# delay_v03.net
KiCad netlist of a schematic drawn in EAGLE
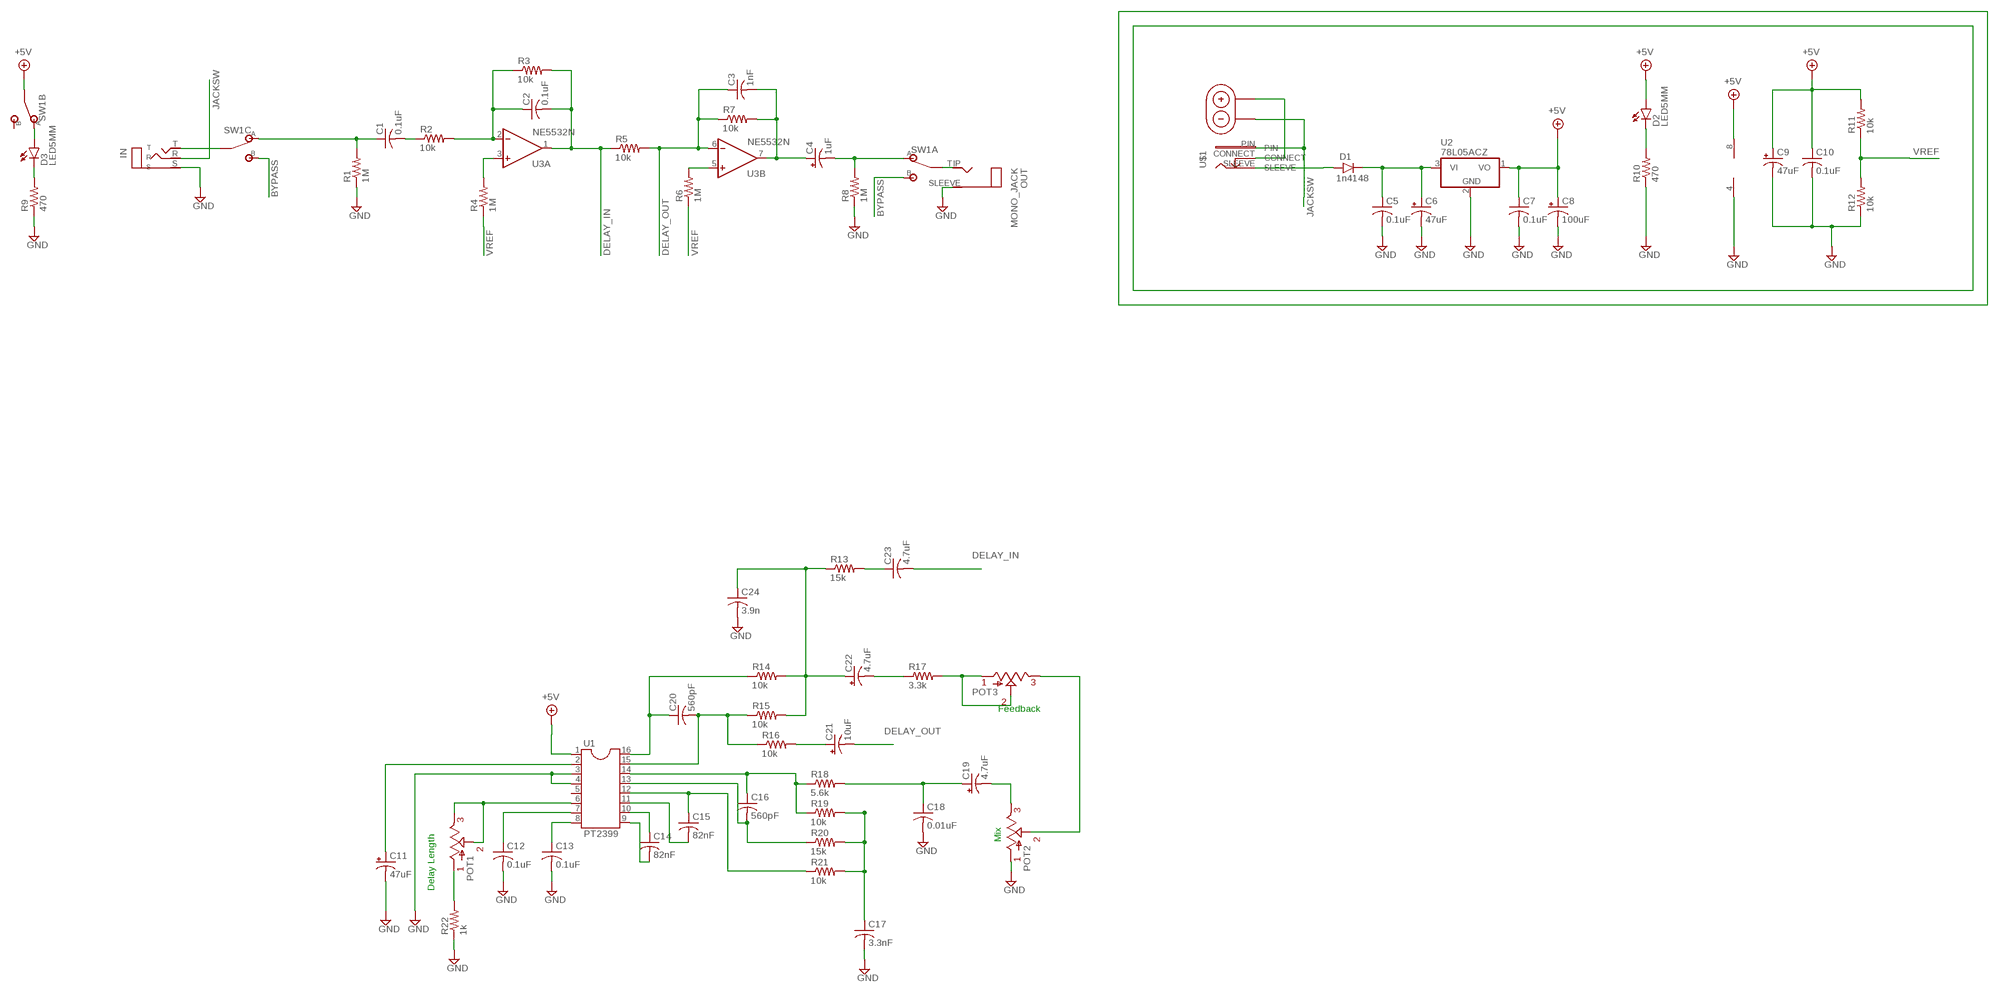
[diagram p0: schematic, sheet 1]

(export (version "E")
  (design (tool "Eeschema 10.0.6"))
  (components
    (comp (ref "C1")
      (value "0.1uF")
      (footprint "eagle-import:C050-035X075")
      (libsource (lib "eagle-import") (part "C-US050-035X075"))
    )
    (comp (ref "C2")
      (value "0.1uF")
      (footprint "eagle-import:C050-035X075")
      (libsource (lib "eagle-import") (part "C-US050-035X075"))
    )
    (comp (ref "C3")
      (value "1nF")
      (footprint "eagle-import:C050-035X075")
      (libsource (lib "eagle-import") (part "C-US050-035X075"))
    )
    (comp (ref "C4")
      (value "1uF")
      (footprint "eagle-import:063_025")
      (libsource (lib "eagle-import") (part "0631"))
    )
    (comp (ref "C5")
      (value "0.1uF")
      (footprint "eagle-import:C050-035X075")
      (libsource (lib "eagle-import") (part "C-US050-035X075"))
    )
    (comp (ref "C6")
      (value "47uF")
      (footprint "eagle-import:063_025")
      (libsource (lib "eagle-import") (part "0631"))
    )
    (comp (ref "C7")
      (value "0.1uF")
      (footprint "eagle-import:C050-035X075")
      (libsource (lib "eagle-import") (part "C-US050-035X075"))
    )
    (comp (ref "C8")
      (value "100uF")
      (footprint "eagle-import:063_025")
      (libsource (lib "eagle-import") (part "0631"))
    )
    (comp (ref "C9")
      (value "47uF")
      (footprint "eagle-import:063_025")
      (libsource (lib "eagle-import") (part "0631"))
    )
    (comp (ref "C10")
      (value "0.1uF")
      (footprint "eagle-import:C050-035X075")
      (libsource (lib "eagle-import") (part "C-US050-035X075"))
    )
    (comp (ref "C11")
      (value "47uF")
      (footprint "eagle-import:063_025")
      (libsource (lib "eagle-import") (part "0631"))
    )
    (comp (ref "C12")
      (value "0.1uF")
      (footprint "eagle-import:C050-035X075")
      (libsource (lib "eagle-import") (part "C-US050-035X075"))
    )
    (comp (ref "C13")
      (value "0.1uF")
      (footprint "eagle-import:C050-035X075")
      (libsource (lib "eagle-import") (part "C-US050-035X075"))
    )
    (comp (ref "C14")
      (value "82nF")
      (footprint "eagle-import:C050-035X075")
      (libsource (lib "eagle-import") (part "C-US050-035X075"))
    )
    (comp (ref "C15")
      (value "82nF")
      (footprint "eagle-import:C050-035X075")
      (libsource (lib "eagle-import") (part "C-US050-035X075"))
    )
    (comp (ref "C16")
      (value "560pF")
      (footprint "eagle-import:C050-035X075")
      (libsource (lib "eagle-import") (part "C-US050-035X075"))
    )
    (comp (ref "C17")
      (value "3.3nF")
      (footprint "eagle-import:C050-035X075")
      (libsource (lib "eagle-import") (part "C-US050-035X075"))
    )
    (comp (ref "C18")
      (value "0.01uF")
      (footprint "eagle-import:C050-035X075")
      (libsource (lib "eagle-import") (part "C-US050-035X075"))
    )
    (comp (ref "C19")
      (value "4.7uF")
      (footprint "eagle-import:063_025")
      (libsource (lib "eagle-import") (part "0631"))
    )
    (comp (ref "C20")
      (value "560pF")
      (footprint "eagle-import:C050-035X075")
      (libsource (lib "eagle-import") (part "C-US050-035X075"))
    )
    (comp (ref "C21")
      (value "10uF")
      (footprint "eagle-import:063_025")
      (libsource (lib "eagle-import") (part "0631"))
    )
    (comp (ref "C22")
      (value "4.7uF")
      (footprint "eagle-import:063_025")
      (libsource (lib "eagle-import") (part "0631"))
    )
    (comp (ref "C23")
      (value "4.7uF")
      (footprint "eagle-import:C050-035X075")
      (libsource (lib "eagle-import") (part "C-US050-035X075"))
    )
    (comp (ref "C24")
      (value "3.9n")
      (footprint "eagle-import:C050-035X075")
      (libsource (lib "eagle-import") (part "C-US050-035X075"))
    )
    (comp (ref "D1")
      (value "1n4148")
      (footprint "eagle-import:DO41-3")
      (libsource (lib "eagle-import") (part "1N400X.3"))
    )
    (comp (ref "D2")
      (value "LED5MM")
      (footprint "eagle-import:LED5MM")
      (libsource (lib "eagle-import") (part "LED5MM"))
    )
    (comp (ref "D3")
      (value "LED5MM")
      (footprint "eagle-import:LED5MM")
      (libsource (lib "eagle-import") (part "LED5MM"))
    )
    (comp (ref "IN")
      (value "STEREO_JACK")
      (footprint "eagle-import:STEREO_JACK")
      (libsource (lib "eagle-import") (part "STEREO_JACK"))
    )
    (comp (ref "OUT")
      (value "MONO_JACK")
      (footprint "eagle-import:MONO_JACK")
      (libsource (lib "eagle-import") (part "MONO_JACK"))
    )
    (comp (ref "POT1")
      (value "POT")
      (footprint "eagle-import:POT")
      (libsource (lib "eagle-import") (part "POT"))
    )
    (comp (ref "POT2")
      (value "POT")
      (footprint "eagle-import:POT")
      (libsource (lib "eagle-import") (part "POT"))
    )
    (comp (ref "POT3")
      (value "POT")
      (footprint "eagle-import:POT")
      (libsource (lib "eagle-import") (part "POT"))
    )
    (comp (ref "R1")
      (value "1M")
      (footprint "eagle-import:RESISTOR")
      (libsource (lib "eagle-import") (part "RESISTOR"))
    )
    (comp (ref "R2")
      (value "10k")
      (footprint "eagle-import:RESISTOR")
      (libsource (lib "eagle-import") (part "RESISTOR"))
    )
    (comp (ref "R3")
      (value "10k")
      (footprint "eagle-import:RESISTOR")
      (libsource (lib "eagle-import") (part "RESISTOR"))
    )
    (comp (ref "R4")
      (value "1M")
      (footprint "eagle-import:RESISTOR")
      (libsource (lib "eagle-import") (part "RESISTOR"))
    )
    (comp (ref "R5")
      (value "10k")
      (footprint "eagle-import:RESISTOR")
      (libsource (lib "eagle-import") (part "RESISTOR"))
    )
    (comp (ref "R6")
      (value "1M")
      (footprint "eagle-import:RESISTOR")
      (libsource (lib "eagle-import") (part "RESISTOR"))
    )
    (comp (ref "R7")
      (value "10k")
      (footprint "eagle-import:RESISTOR")
      (libsource (lib "eagle-import") (part "RESISTOR"))
    )
    (comp (ref "R8")
      (value "1M")
      (footprint "eagle-import:RESISTOR")
      (libsource (lib "eagle-import") (part "RESISTOR"))
    )
    (comp (ref "R9")
      (value "470")
      (footprint "eagle-import:RESISTOR")
      (libsource (lib "eagle-import") (part "RESISTOR"))
    )
    (comp (ref "R10")
      (value "470")
      (footprint "eagle-import:RESISTOR")
      (libsource (lib "eagle-import") (part "RESISTOR"))
    )
    (comp (ref "R11")
      (value "10k")
      (footprint "eagle-import:RESISTOR")
      (libsource (lib "eagle-import") (part "RESISTOR"))
    )
    (comp (ref "R12")
      (value "10k")
      (footprint "eagle-import:RESISTOR")
      (libsource (lib "eagle-import") (part "RESISTOR"))
    )
    (comp (ref "R13")
      (value "15k")
      (footprint "eagle-import:RESISTOR")
      (libsource (lib "eagle-import") (part "RESISTOR"))
    )
    (comp (ref "R14")
      (value "10k")
      (footprint "eagle-import:RESISTOR")
      (libsource (lib "eagle-import") (part "RESISTOR"))
    )
    (comp (ref "R15")
      (value "10k")
      (footprint "eagle-import:RESISTOR")
      (libsource (lib "eagle-import") (part "RESISTOR"))
    )
    (comp (ref "R16")
      (value "10k")
      (footprint "eagle-import:RESISTOR")
      (libsource (lib "eagle-import") (part "RESISTOR"))
    )
    (comp (ref "R17")
      (value "3.3k")
      (footprint "eagle-import:RESISTOR")
      (libsource (lib "eagle-import") (part "RESISTOR"))
    )
    (comp (ref "R18")
      (value "5.6k")
      (footprint "eagle-import:RESISTOR")
      (libsource (lib "eagle-import") (part "RESISTOR"))
    )
    (comp (ref "R19")
      (value "10k")
      (footprint "eagle-import:RESISTOR")
      (libsource (lib "eagle-import") (part "RESISTOR"))
    )
    (comp (ref "R20")
      (value "15k")
      (footprint "eagle-import:RESISTOR")
      (libsource (lib "eagle-import") (part "RESISTOR"))
    )
    (comp (ref "R21")
      (value "10k")
      (footprint "eagle-import:RESISTOR")
      (libsource (lib "eagle-import") (part "RESISTOR"))
    )
    (comp (ref "R22")
      (value "1k")
      (footprint "eagle-import:RESISTOR")
      (libsource (lib "eagle-import") (part "RESISTOR"))
    )
    (comp (ref "SW1")
      (value "3PDT")
      (footprint "eagle-import:3PDT")
      (libsource (lib "eagle-import") (part "3PDT"))
    )
    (comp (ref "U$1")
      (value "DC_JACK_OFFBOARD")
      (footprint "eagle-import:DC_JACK_OFFBOARD")
      (libsource (lib "eagle-import") (part "DC_JACK_OFFBOARD"))
    )
    (comp (ref "U$2")
      (value "9V_BATTERY_CLIP")
      (footprint "eagle-import:9V_BATTERY")
      (libsource (lib "eagle-import") (part "9V_BATTERY_CLIP"))
    )
    (comp (ref "U1")
      (value "PT2399")
      (footprint "eagle-import:SOCKET-16")
      (libsource (lib "eagle-import") (part "DIL16S"))
    )
    (comp (ref "U2")
      (value "78L05ACZ")
      (footprint "eagle-import:TO-92")
      (libsource (lib "eagle-import") (part "78L05ACZ"))
    )
    (comp (ref "U3")
      (value "NE5532N")
      (footprint "eagle-import:DIL08")
      (libsource (lib "eagle-import") (part "NE5532N"))
    )
  )
  (nets
    (net (code "1") (name "+5V") (class "Default")
      (node (ref "C10") (pin "1") (pinfunction "1_1") (pintype "passive"))
      (node (ref "C7") (pin "1") (pinfunction "1_1") (pintype "passive"))
      (node (ref "C8") (pin "+") (pinfunction "+_+") (pintype "passive"))
      (node (ref "C9") (pin "+") (pinfunction "+_+") (pintype "passive"))
      (node (ref "D2") (pin "A") (pinfunction "A_A") (pintype "passive"))
      (node (ref "R11") (pin "2") (pinfunction "2_2") (pintype "passive"))
      (node (ref "SW1") (pin "B2") (pinfunction "COM_B2") (pintype "passive"))
      (node (ref "U1") (pin "1") (pinfunction "1_1") (pintype "passive"))
      (node (ref "U2") (pin "1") (pinfunction "VO_1") (pintype "passive"))
      (node (ref "U3") (pin "8") (pinfunction "V+_8") (pintype "power_in"))
    )
    (net (code "2") (name "/BYPASS") (class "Default")
      (node (ref "SW1") (pin "A3") (pinfunction "B_A3") (pintype "passive"))
      (node (ref "SW1") (pin "C3") (pinfunction "B_C3") (pintype "passive"))
    )
    (net (code "3") (name "/DELAY_IN") (class "Default")
      (node (ref "C2") (pin "2") (pinfunction "2_2") (pintype "passive"))
      (node (ref "C23") (pin "2") (pinfunction "2_2") (pintype "passive"))
      (node (ref "R3") (pin "2") (pinfunction "2_2") (pintype "passive"))
      (node (ref "R5") (pin "1") (pinfunction "1_1") (pintype "passive"))
      (node (ref "U3") (pin "1") (pinfunction "OUT_1") (pintype "output"))
    )
    (net (code "4") (name "/DELAY_OUT") (class "Default")
      (node (ref "C21") (pin "-") (pinfunction "-_-") (pintype "passive"))
      (node (ref "C3") (pin "1") (pinfunction "1_1") (pintype "passive"))
      (node (ref "R5") (pin "2") (pinfunction "2_2") (pintype "passive"))
      (node (ref "R7") (pin "1") (pinfunction "1_1") (pintype "passive"))
      (node (ref "U3") (pin "6") (pinfunction "-IN_6") (pintype "input"))
    )
    (net (code "5") (name "/JACKSW") (class "Default")
      (node (ref "IN") (pin "R") (pinfunction "R_R") (pintype "passive"))
      (node (ref "U$1") (pin "PIN") (pinfunction "PIN_PIN") (pintype "bidirectional"))
      (node (ref "U$2") (pin "9V_BATTERY_-") (pinfunction "9V_BATTERY_-_9V_BATTERY_-") (pintype "power_in"))
    )
    (net (code "6") (name "/VREF") (class "Default")
      (node (ref "R11") (pin "1") (pinfunction "1_1") (pintype "passive"))
      (node (ref "R12") (pin "2") (pinfunction "2_2") (pintype "passive"))
      (node (ref "R4") (pin "1") (pinfunction "1_1") (pintype "passive"))
      (node (ref "R6") (pin "1") (pinfunction "1_1") (pintype "passive"))
    )
    (net (code "7") (name "GND") (class "Default")
      (node (ref "C10") (pin "2") (pinfunction "2_2") (pintype "passive"))
      (node (ref "C11") (pin "-") (pinfunction "-_-") (pintype "passive"))
      (node (ref "C12") (pin "2") (pinfunction "2_2") (pintype "passive"))
      (node (ref "C13") (pin "2") (pinfunction "2_2") (pintype "passive"))
      (node (ref "C17") (pin "2") (pinfunction "2_2") (pintype "passive"))
      (node (ref "C18") (pin "2") (pinfunction "2_2") (pintype "passive"))
      (node (ref "C24") (pin "2") (pinfunction "2_2") (pintype "passive"))
      (node (ref "C5") (pin "2") (pinfunction "2_2") (pintype "passive"))
      (node (ref "C6") (pin "-") (pinfunction "-_-") (pintype "passive"))
      (node (ref "C7") (pin "2") (pinfunction "2_2") (pintype "passive"))
      (node (ref "C8") (pin "-") (pinfunction "-_-") (pintype "passive"))
      (node (ref "C9") (pin "-") (pinfunction "-_-") (pintype "passive"))
      (node (ref "IN") (pin "S") (pinfunction "S_S") (pintype "passive"))
      (node (ref "OUT") (pin "SLEEVE") (pinfunction "SLEEVE_SLEEVE") (pintype "passive"))
      (node (ref "POT2") (pin "1") (pinfunction "1_1") (pintype "passive"))
      (node (ref "R1") (pin "1") (pinfunction "1_1") (pintype "passive"))
      (node (ref "R10") (pin "1") (pinfunction "1_1") (pintype "passive"))
      (node (ref "R12") (pin "1") (pinfunction "1_1") (pintype "passive"))
      (node (ref "R22") (pin "1") (pinfunction "1_1") (pintype "passive"))
      (node (ref "R8") (pin "1") (pinfunction "1_1") (pintype "passive"))
      (node (ref "R9") (pin "1") (pinfunction "1_1") (pintype "passive"))
      (node (ref "U1") (pin "3") (pinfunction "3_3") (pintype "passive"))
      (node (ref "U1") (pin "4") (pinfunction "4_4") (pintype "passive"))
      (node (ref "U2") (pin "2") (pinfunction "GND_2") (pintype "passive"))
      (node (ref "U3") (pin "4") (pinfunction "V-_4") (pintype "power_in"))
    )
    (net (code "8") (name "Net-(C1-Pad2)") (class "Default")
      (node (ref "C1") (pin "2") (pinfunction "2_2") (pintype "passive"))
      (node (ref "R2") (pin "1") (pinfunction "1_1") (pintype "passive"))
    )
    (net (code "9") (name "Net-(C11-Pad+)") (class "Default")
      (node (ref "C11") (pin "+") (pinfunction "+_+") (pintype "passive"))
      (node (ref "U1") (pin "2") (pinfunction "2_2") (pintype "passive"))
    )
    (net (code "10") (name "Net-(C12-Pad1)") (class "Default")
      (node (ref "C12") (pin "1") (pinfunction "1_1") (pintype "passive"))
      (node (ref "U1") (pin "7") (pinfunction "7_7") (pintype "passive"))
    )
    (net (code "11") (name "Net-(C13-Pad1)") (class "Default")
      (node (ref "C13") (pin "1") (pinfunction "1_1") (pintype "passive"))
      (node (ref "U1") (pin "8") (pinfunction "8_8") (pintype "passive"))
    )
    (net (code "12") (name "Net-(C14-Pad1)") (class "Default")
      (node (ref "C14") (pin "1") (pinfunction "1_1") (pintype "passive"))
      (node (ref "U1") (pin "10") (pinfunction "10_10") (pintype "passive"))
    )
    (net (code "13") (name "Net-(C14-Pad2)") (class "Default")
      (node (ref "C14") (pin "2") (pinfunction "2_2") (pintype "passive"))
      (node (ref "U1") (pin "9") (pinfunction "9_9") (pintype "passive"))
    )
    (net (code "14") (name "Net-(C15-Pad1)") (class "Default")
      (node (ref "C15") (pin "1") (pinfunction "1_1") (pintype "passive"))
      (node (ref "R21") (pin "1") (pinfunction "1_1") (pintype "passive"))
      (node (ref "U1") (pin "12") (pinfunction "12_12") (pintype "passive"))
    )
    (net (code "15") (name "Net-(C15-Pad2)") (class "Default")
      (node (ref "C15") (pin "2") (pinfunction "2_2") (pintype "passive"))
      (node (ref "U1") (pin "11") (pinfunction "11_11") (pintype "passive"))
    )
    (net (code "16") (name "Net-(C16-Pad1)") (class "Default")
      (node (ref "C16") (pin "1") (pinfunction "1_1") (pintype "passive"))
      (node (ref "R18") (pin "1") (pinfunction "1_1") (pintype "passive"))
      (node (ref "R19") (pin "1") (pinfunction "1_1") (pintype "passive"))
      (node (ref "U1") (pin "14") (pinfunction "14_14") (pintype "passive"))
    )
    (net (code "17") (name "Net-(C16-Pad2)") (class "Default")
      (node (ref "C16") (pin "2") (pinfunction "2_2") (pintype "passive"))
      (node (ref "R20") (pin "1") (pinfunction "1_1") (pintype "passive"))
      (node (ref "U1") (pin "13") (pinfunction "13_13") (pintype "passive"))
    )
    (net (code "18") (name "Net-(C17-Pad1)") (class "Default")
      (node (ref "C17") (pin "1") (pinfunction "1_1") (pintype "passive"))
      (node (ref "R19") (pin "2") (pinfunction "2_2") (pintype "passive"))
      (node (ref "R20") (pin "2") (pinfunction "2_2") (pintype "passive"))
      (node (ref "R21") (pin "2") (pinfunction "2_2") (pintype "passive"))
    )
    (net (code "19") (name "Net-(C18-Pad1)") (class "Default")
      (node (ref "C18") (pin "1") (pinfunction "1_1") (pintype "passive"))
      (node (ref "C19") (pin "+") (pinfunction "+_+") (pintype "passive"))
      (node (ref "R18") (pin "2") (pinfunction "2_2") (pintype "passive"))
    )
    (net (code "20") (name "Net-(C19-Pad-)") (class "Default")
      (node (ref "C19") (pin "-") (pinfunction "-_-") (pintype "passive"))
      (node (ref "POT2") (pin "3") (pinfunction "3_3") (pintype "passive"))
    )
    (net (code "21") (name "Net-(C20-Pad1)") (class "Default")
      (node (ref "C20") (pin "1") (pinfunction "1_1") (pintype "passive"))
      (node (ref "R14") (pin "1") (pinfunction "1_1") (pintype "passive"))
      (node (ref "U1") (pin "16") (pinfunction "16_16") (pintype "passive"))
    )
    (net (code "22") (name "Net-(C20-Pad2)") (class "Default")
      (node (ref "C20") (pin "2") (pinfunction "2_2") (pintype "passive"))
      (node (ref "R15") (pin "1") (pinfunction "1_1") (pintype "passive"))
      (node (ref "R16") (pin "1") (pinfunction "1_1") (pintype "passive"))
      (node (ref "U1") (pin "15") (pinfunction "15_15") (pintype "passive"))
    )
    (net (code "23") (name "Net-(C21-Pad+)") (class "Default")
      (node (ref "C21") (pin "+") (pinfunction "+_+") (pintype "passive"))
      (node (ref "R16") (pin "2") (pinfunction "2_2") (pintype "passive"))
    )
    (net (code "24") (name "Net-(C22-Pad+)") (class "Default")
      (node (ref "C22") (pin "+") (pinfunction "+_+") (pintype "passive"))
      (node (ref "C24") (pin "1") (pinfunction "1_1") (pintype "passive"))
      (node (ref "R13") (pin "1") (pinfunction "1_1") (pintype "passive"))
      (node (ref "R14") (pin "2") (pinfunction "2_2") (pintype "passive"))
      (node (ref "R15") (pin "2") (pinfunction "2_2") (pintype "passive"))
    )
    (net (code "25") (name "Net-(C22-Pad-)") (class "Default")
      (node (ref "C22") (pin "-") (pinfunction "-_-") (pintype "passive"))
      (node (ref "R17") (pin "1") (pinfunction "1_1") (pintype "passive"))
    )
    (net (code "26") (name "Net-(C23-Pad1)") (class "Default")
      (node (ref "C23") (pin "1") (pinfunction "1_1") (pintype "passive"))
      (node (ref "R13") (pin "2") (pinfunction "2_2") (pintype "passive"))
    )
    (net (code "27") (name "Net-(D1-PadA)") (class "Default")
      (node (ref "D1") (pin "A") (pinfunction "A_A") (pintype "passive"))
      (node (ref "U$1") (pin "SLEEVE") (pinfunction "SLEEVE_SLEEVE") (pintype "bidirectional"))
    )
    (net (code "28") (name "Net-(D2-C)") (class "Default")
      (node (ref "D2") (pin "K") (pinfunction "C_K") (pintype "passive"))
      (node (ref "R10") (pin "2") (pinfunction "2_2") (pintype "passive"))
    )
    (net (code "29") (name "Net-(D3-C)") (class "Default")
      (node (ref "D3") (pin "K") (pinfunction "C_K") (pintype "passive"))
      (node (ref "R9") (pin "2") (pinfunction "2_2") (pintype "passive"))
    )
    (net (code "30") (name "Net-(POT1-Pad1)") (class "Default")
      (node (ref "POT1") (pin "1") (pinfunction "1_1") (pintype "passive"))
      (node (ref "R22") (pin "2") (pinfunction "2_2") (pintype "passive"))
    )
    (net (code "31") (name "Net-(POT1-Pad2)") (class "Default")
      (node (ref "POT1") (pin "2") (pinfunction "2_2") (pintype "passive"))
      (node (ref "POT1") (pin "3") (pinfunction "3_3") (pintype "passive"))
      (node (ref "U1") (pin "6") (pinfunction "6_6") (pintype "passive"))
    )
    (net (code "32") (name "Net-(POT2-Pad2)") (class "Default")
      (node (ref "POT2") (pin "2") (pinfunction "2_2") (pintype "passive"))
      (node (ref "POT3") (pin "3") (pinfunction "3_3") (pintype "passive"))
    )
    (net (code "33") (name "Net-(POT3-Pad1)") (class "Default")
      (node (ref "POT3") (pin "1") (pinfunction "1_1") (pintype "passive"))
      (node (ref "POT3") (pin "2") (pinfunction "2_2") (pintype "passive"))
      (node (ref "R17") (pin "2") (pinfunction "2_2") (pintype "passive"))
    )
    (net (code "34") (name "Net-(SW1A-A)") (class "Default")
      (node (ref "C4") (pin "-") (pinfunction "-_-") (pintype "passive"))
      (node (ref "R8") (pin "2") (pinfunction "2_2") (pintype "passive"))
      (node (ref "SW1") (pin "A1") (pinfunction "A_A1") (pintype "passive"))
    )
    (net (code "35") (name "Net-(SW1A-COM)") (class "Default")
      (node (ref "OUT") (pin "TIP") (pinfunction "TIP_TIP") (pintype "passive"))
      (node (ref "SW1") (pin "A2") (pinfunction "COM_A2") (pintype "passive"))
    )
    (net (code "36") (name "Net-(SW1B-A)") (class "Default")
      (node (ref "D3") (pin "A") (pinfunction "A_A") (pintype "passive"))
      (node (ref "SW1") (pin "B1") (pinfunction "A_B1") (pintype "passive"))
    )
    (net (code "37") (name "Net-(SW1C-A)") (class "Default")
      (node (ref "C1") (pin "1") (pinfunction "1_1") (pintype "passive"))
      (node (ref "R1") (pin "2") (pinfunction "2_2") (pintype "passive"))
      (node (ref "SW1") (pin "C1") (pinfunction "A_C1") (pintype "passive"))
    )
    (net (code "38") (name "Net-(SW1C-COM)") (class "Default")
      (node (ref "IN") (pin "T") (pinfunction "T_T") (pintype "passive"))
      (node (ref "SW1") (pin "C2") (pinfunction "COM_C2") (pintype "passive"))
    )
    (net (code "39") (name "Net-(U$1-PadCONNECT)") (class "Default")
      (node (ref "U$1") (pin "CONNECT") (pinfunction "CONNECT_CONNECT") (pintype "bidirectional"))
      (node (ref "U$2") (pin "9V_BATTERY_+") (pinfunction "9V_BATTERY_+_9V_BATTERY_+") (pintype "power_in"))
    )
    (net (code "40") (name "Net-(U2-VI)") (class "Default")
      (node (ref "C5") (pin "1") (pinfunction "1_1") (pintype "passive"))
      (node (ref "C6") (pin "+") (pinfunction "+_+") (pintype "passive"))
      (node (ref "D1") (pin "C") (pinfunction "C_C") (pintype "passive"))
      (node (ref "U2") (pin "3") (pinfunction "VI_3") (pintype "input"))
    )
    (net (code "41") (name "Net-(U3A-+IN)") (class "Default")
      (node (ref "R4") (pin "2") (pinfunction "2_2") (pintype "passive"))
      (node (ref "U3") (pin "3") (pinfunction "+IN_3") (pintype "input"))
    )
    (net (code "42") (name "Net-(U3A--IN)") (class "Default")
      (node (ref "C2") (pin "1") (pinfunction "1_1") (pintype "passive"))
      (node (ref "R2") (pin "2") (pinfunction "2_2") (pintype "passive"))
      (node (ref "R3") (pin "1") (pinfunction "1_1") (pintype "passive"))
      (node (ref "U3") (pin "2") (pinfunction "-IN_2") (pintype "input"))
    )
    (net (code "43") (name "Net-(U3B-+IN)") (class "Default")
      (node (ref "R6") (pin "2") (pinfunction "2_2") (pintype "passive"))
      (node (ref "U3") (pin "5") (pinfunction "+IN_5") (pintype "input"))
    )
    (net (code "44") (name "Net-(U3B-OUT)") (class "Default")
      (node (ref "C3") (pin "2") (pinfunction "2_2") (pintype "passive"))
      (node (ref "C4") (pin "+") (pinfunction "+_+") (pintype "passive"))
      (node (ref "R7") (pin "2") (pinfunction "2_2") (pintype "passive"))
      (node (ref "U3") (pin "7") (pinfunction "OUT_7") (pintype "output"))
    )
    (net (code "45") (name "unconnected-(SW1B-B-PadB3)") (class "Default")
      (node (ref "SW1") (pin "B3") (pinfunction "B_B3") (pintype "passive"))
    )
    (net (code "46") (name "unconnected-(U1-Pad5)") (class "Default")
      (node (ref "U1") (pin "5") (pinfunction "5_5") (pintype "passive"))
    )
  )
)
